# buck_simulation_1.net
KiCad netlist of a schematic drawn in Altium Designer
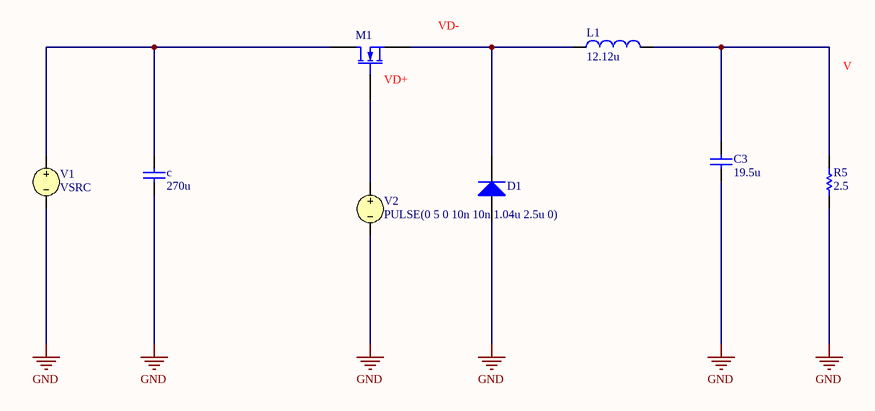
[diagram p0: buck (simulation) (1).SchDoc]

(export (version "E")
  (design (tool "Eeschema 10.0.6"))
  (components
    (comp (ref "c")
      (value "270u")
      (description "Capacitor")
      (libsource (lib "Simulation Generic Components") (part "Capacitor"))
    )
    (comp (ref "C3")
      (value "19.5u")
      (description "Capacitor")
      (libsource (lib "Simulation Generic Components") (part "Capacitor"))
    )
    (comp (ref "D1") (value "Diode") (libsource (lib "Simulation Generic Components") (part "Diode")))
    (comp (ref "L1")
      (value "12.12u")
      (description "Inductor")
      (libsource (lib "Simulation Generic Components") (part "Inductor"))
    )
    (comp (ref "M1")
      (value "N-channel Power MOSFET VDMOS Model")
      (libsource (lib "Simulation Generic Components") (part "MOSFET N-ch VDMOS"))
    )
    (comp (ref "R5")
      (value "2.5")
      (description "Resistor")
      (libsource (lib "Simulation Generic Components") (part "Resistor"))
    )
    (comp (ref "V1")
      (value "VSRC")
      (description "Voltage Source")
      (fields (field (name "PUBLISHER") "Altium Limited"))
      (libsource (lib "Simulation Generic Components") (part "VSRC"))
    )
    (comp (ref "V2")
      (value "PULSE(0 5 0 10n 10n 1.04u 2.5u 0)")
      (description "Voltage Source")
      (fields (field (name "PUBLISHER") "Altium Limited"))
      (libsource (lib "Simulation Generic Components") (part "VSRC"))
    )
  )
  (nets
    (net (code "1") (name "GND") (class "Default")
      (node (ref "C3") (pin "1") (pinfunction "1_1") (pintype "passive"))
      (node (ref "D1") (pin "1") (pinfunction "A_1") (pintype "passive"))
      (node (ref "R5") (pin "1") (pinfunction "1_1") (pintype "passive"))
      (node (ref "V1") (pin "2") (pinfunction "2_2") (pintype "passive"))
      (node (ref "V2") (pin "2") (pinfunction "2_2") (pintype "passive"))
      (node (ref "c") (pin "1") (pinfunction "1_1") (pintype "passive"))
    )
    (net (code "2") (name "Net-(C3-Pad2)") (class "Default")
      (node (ref "C3") (pin "2") (pinfunction "2_2") (pintype "passive"))
      (node (ref "L1") (pin "2") (pinfunction "2_2") (pintype "passive"))
      (node (ref "R5") (pin "2") (pinfunction "2_2") (pintype "passive"))
    )
    (net (code "3") (name "Net-(D1-K)") (class "Default")
      (node (ref "D1") (pin "2") (pinfunction "K_2") (pintype "passive"))
      (node (ref "L1") (pin "1") (pinfunction "1_1") (pintype "passive"))
      (node (ref "M1") (pin "3") (pinfunction "S_3") (pintype "passive"))
    )
    (net (code "4") (name "Net-(M1-D)") (class "Default")
      (node (ref "M1") (pin "1") (pinfunction "D_1") (pintype "passive"))
      (node (ref "V1") (pin "1") (pinfunction "1_1") (pintype "passive"))
      (node (ref "c") (pin "2") (pinfunction "2_2") (pintype "passive"))
    )
    (net (code "5") (name "Net-(M1-G)") (class "Default")
      (node (ref "M1") (pin "2") (pinfunction "G_2") (pintype "passive"))
      (node (ref "V2") (pin "1") (pinfunction "1_1") (pintype "passive"))
    )
  )
)
